# receiver_lify.net
KiCad netlist of a schematic drawn in EAGLE
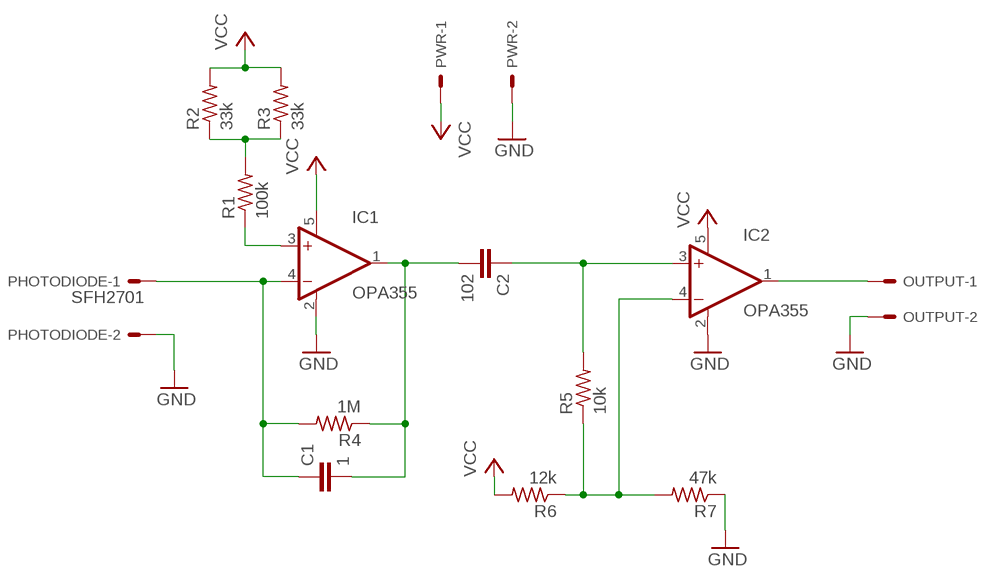
[diagram p0: schematic, sheet 1]

(export (version "E")
  (design (tool "Eeschema 10.0.6"))
  (components
    (comp (ref "C1")
      (value "1")
      (footprint "eagle-import:C050-025X075")
      (libsource (lib "eagle-import") (part "C-EU050-025X075"))
    )
    (comp (ref "C2")
      (value "102")
      (footprint "eagle-import:C050-025X075")
      (libsource (lib "eagle-import") (part "C-EU050-025X075"))
    )
    (comp (ref "IC1")
      (value "OPA355")
      (footprint "eagle-import:SOT23-5")
      (libsource (lib "eagle-import") (part "OPA658N"))
    )
    (comp (ref "IC2")
      (value "OPA355")
      (footprint "eagle-import:SOT23-5")
      (libsource (lib "eagle-import") (part "OPA658N"))
    )
    (comp (ref "OUTPUT")
      (value "22-23-2021")
      (footprint "eagle-import:22-23-2021")
      (fields (field (name "MF") "MOLEX"))
      (libsource (lib "eagle-import") (part "22-23-2021"))
    )
    (comp (ref "PHOTODIODE")
      (value "SFH2701")
      (footprint "eagle-import:22-23-2021")
      (fields (field (name "MF") "MOLEX") (field (name "MPN") "22-23-2021"))
      (libsource (lib "eagle-import") (part "22-23-2021"))
    )
    (comp (ref "PWR")
      (value "22-23-2021")
      (footprint "eagle-import:22-23-2021")
      (fields (field (name "MF") "MOLEX"))
      (libsource (lib "eagle-import") (part "22-23-2021"))
    )
    (comp (ref "R1")
      (value "100k")
      (footprint "eagle-import:0204_7")
      (libsource (lib "eagle-import") (part "R-US_0204/7"))
    )
    (comp (ref "R2")
      (value "33k")
      (footprint "eagle-import:0204_7")
      (libsource (lib "eagle-import") (part "R-US_0204/7"))
    )
    (comp (ref "R3")
      (value "33k")
      (footprint "eagle-import:0204_7")
      (libsource (lib "eagle-import") (part "R-US_0204/7"))
    )
    (comp (ref "R4")
      (value "1M")
      (footprint "eagle-import:0204_7")
      (libsource (lib "eagle-import") (part "R-US_0204/7"))
    )
    (comp (ref "R5")
      (value "10k")
      (footprint "eagle-import:0204_7")
      (libsource (lib "eagle-import") (part "R-US_0204/7"))
    )
    (comp (ref "R6")
      (value "12k")
      (footprint "eagle-import:0204_7")
      (libsource (lib "eagle-import") (part "R-US_0204/7"))
    )
    (comp (ref "R7")
      (value "47k")
      (footprint "eagle-import:0204_7")
      (libsource (lib "eagle-import") (part "R-US_0204/7"))
    )
  )
  (nets
    (net (code "1") (name "GND") (class "Default")
      (node (ref "IC1") (pin "2") (pinfunction "V-_2") (pintype "power_in"))
      (node (ref "IC2") (pin "2") (pinfunction "V-_2") (pintype "power_in"))
      (node (ref "OUTPUT") (pin "2") (pinfunction "S_2") (pintype "passive"))
      (node (ref "PHOTODIODE") (pin "2") (pinfunction "S_2") (pintype "passive"))
      (node (ref "PWR") (pin "2") (pinfunction "S_2") (pintype "passive"))
      (node (ref "R7") (pin "1") (pinfunction "1_1") (pintype "passive"))
    )
    (net (code "2") (name "Net-(IC1-+IN)") (class "Default")
      (node (ref "IC1") (pin "3") (pinfunction "+IN_3") (pintype "input"))
      (node (ref "R1") (pin "1") (pinfunction "1_1") (pintype "passive"))
    )
    (net (code "3") (name "Net-(IC1--IN)") (class "Default")
      (node (ref "C1") (pin "1") (pinfunction "1_1") (pintype "passive"))
      (node (ref "IC1") (pin "4") (pinfunction "-IN_4") (pintype "input"))
      (node (ref "PHOTODIODE") (pin "1") (pinfunction "S_1") (pintype "passive"))
      (node (ref "R4") (pin "2") (pinfunction "2_2") (pintype "passive"))
    )
    (net (code "4") (name "Net-(IC1-OUT)") (class "Default")
      (node (ref "C1") (pin "2") (pinfunction "2_2") (pintype "passive"))
      (node (ref "C2") (pin "2") (pinfunction "2_2") (pintype "passive"))
      (node (ref "IC1") (pin "1") (pinfunction "OUT_1") (pintype "output"))
      (node (ref "R4") (pin "1") (pinfunction "1_1") (pintype "passive"))
    )
    (net (code "5") (name "Net-(IC2-+IN)") (class "Default")
      (node (ref "C2") (pin "1") (pinfunction "1_1") (pintype "passive"))
      (node (ref "IC2") (pin "3") (pinfunction "+IN_3") (pintype "input"))
      (node (ref "R5") (pin "2") (pinfunction "2_2") (pintype "passive"))
    )
    (net (code "6") (name "Net-(IC2--IN)") (class "Default")
      (node (ref "IC2") (pin "4") (pinfunction "-IN_4") (pintype "input"))
      (node (ref "R5") (pin "1") (pinfunction "1_1") (pintype "passive"))
      (node (ref "R6") (pin "1") (pinfunction "1_1") (pintype "passive"))
      (node (ref "R7") (pin "2") (pinfunction "2_2") (pintype "passive"))
    )
    (net (code "7") (name "Net-(IC2-OUT)") (class "Default")
      (node (ref "IC2") (pin "1") (pinfunction "OUT_1") (pintype "output"))
      (node (ref "OUTPUT") (pin "1") (pinfunction "S_1") (pintype "passive"))
    )
    (net (code "8") (name "Net-(R1-Pad2)") (class "Default")
      (node (ref "R1") (pin "2") (pinfunction "2_2") (pintype "passive"))
      (node (ref "R2") (pin "1") (pinfunction "1_1") (pintype "passive"))
      (node (ref "R3") (pin "1") (pinfunction "1_1") (pintype "passive"))
    )
    (net (code "9") (name "VCC") (class "Default")
      (node (ref "IC1") (pin "5") (pinfunction "V+_5") (pintype "power_in"))
      (node (ref "IC2") (pin "5") (pinfunction "V+_5") (pintype "power_in"))
      (node (ref "PWR") (pin "1") (pinfunction "S_1") (pintype "passive"))
      (node (ref "R2") (pin "2") (pinfunction "2_2") (pintype "passive"))
      (node (ref "R3") (pin "2") (pinfunction "2_2") (pintype "passive"))
      (node (ref "R6") (pin "2") (pinfunction "2_2") (pintype "passive"))
    )
  )
)
